# Schema_Attiny_composant.net
KiCad netlist of a schematic drawn in Altium Designer
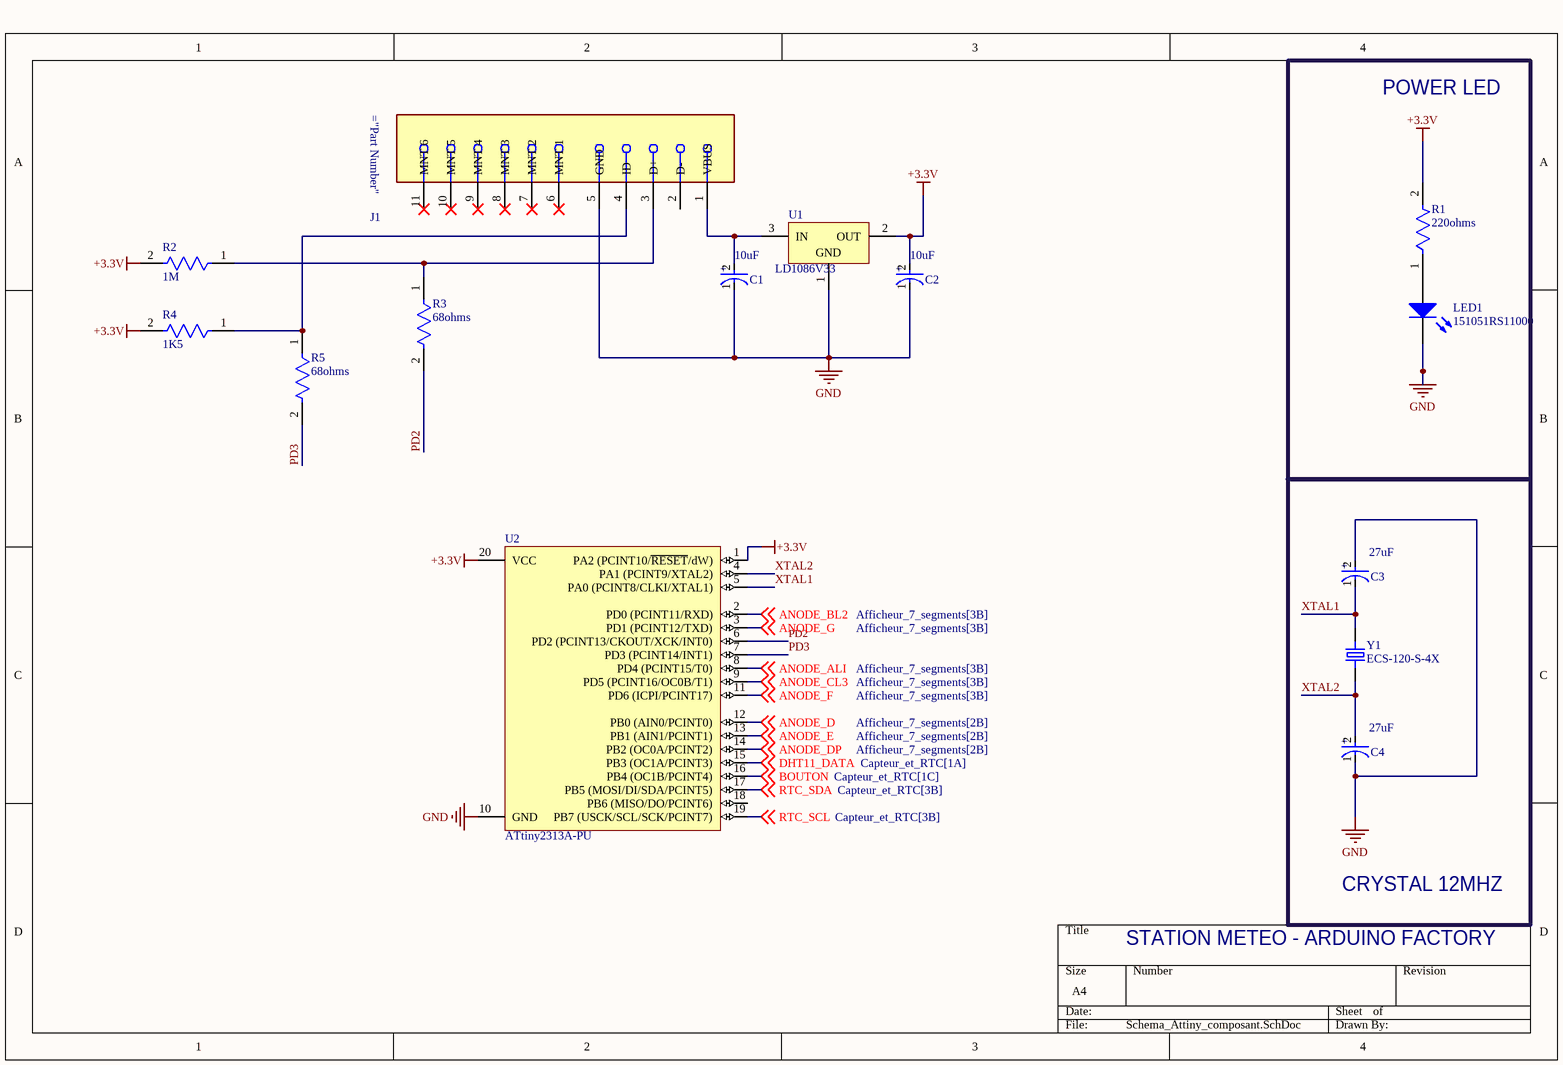
[diagram p0: Schema_Attiny_composant.SchDoc]

(export (version "E")
  (design (tool "Eeschema 10.0.6"))
  (components
    (comp (ref "C1")
      (value "10uF")
      (footprint "Rubycon_0_MFG")
      (libsource (lib "Cap_Rubycon_35ZLH100MEFC6_3X11_eec") (part "35ZLH100MEFC6_3X11"))
    )
    (comp (ref "C2")
      (value "10uF")
      (footprint "Rubycon_0_MFG")
      (libsource (lib "Cap_Rubycon_35ZLH100MEFC6_3X11_eec") (part "35ZLH100MEFC6_3X11"))
    )
    (comp (ref "C3")
      (value "27uF")
      (footprint "Rubycon_0_MFG")
      (libsource (lib "Cap_Rubycon_35ZLH100MEFC6_3X11_eec") (part "35ZLH100MEFC6_3X11"))
    )
    (comp (ref "C4")
      (value "27uF")
      (footprint "Rubycon_0_MFG")
      (libsource (lib "Cap_Rubycon_35ZLH100MEFC6_3X11_eec") (part "35ZLH100MEFC6_3X11"))
    )
    (comp (ref "J1")
      (value "105164-0001")
      (footprint "Molex_105164-0001_0")
      (libsource (lib "Conn_Molex_105164-0001_eec") (part "105164-0001"))
    )
    (comp (ref "LED1")
      (value "151051RS11000")
      (footprint "Type 5mm")
      (description "THT LED round mono-color color lens, WL-TMRW, Red")
      (fields (field (name "MANUFACTURER") "Wuerth Elektronik"))
      (libsource (lib "Wuerth_Elektronik_151051RS11000") (part "151051RS11000"))
    )
    (comp (ref "R1")
      (value "220ohms")
      (footprint "Stackpole_Electronics_Inc._CF14JT1K00_0")
      (libsource (lib "Res_Yageo_MF0207FTE52-10K_eec") (part "MF0207FTE52-10K"))
    )
    (comp (ref "R2")
      (value "1M")
      (footprint "Stackpole_Electronics_Inc._CF14JT1K00_0")
      (libsource (lib "Res_Yageo_MF0207FTE52-10K_eec") (part "MF0207FTE52-10K"))
    )
    (comp (ref "R3")
      (value "68ohms")
      (footprint "Stackpole_Electronics_Inc._CF14JT1K00_0")
      (libsource (lib "Res_Yageo_MF0207FTE52-10K_eec") (part "MF0207FTE52-10K"))
    )
    (comp (ref "R4")
      (value "1K5")
      (footprint "Stackpole_Electronics_Inc._CF14JT1K00_0")
      (libsource (lib "Res_Yageo_MF0207FTE52-10K_eec") (part "MF0207FTE52-10K"))
    )
    (comp (ref "R5")
      (value "68ohms")
      (footprint "Stackpole_Electronics_Inc._CF14JT1K00_0")
      (libsource (lib "Res_Yageo_MF0207FTE52-10K_eec") (part "MF0207FTE52-10K"))
    )
    (comp (ref "U1")
      (value "LD1086V33")
      (footprint "TO220")
      (description "1.5A, Low Drop Positive Voltage Regulator, 3.3V, 3-Pin TO-220")
      (libsource (lib "STMicroelectronics_LD1086V33") (part "LD1086V33"))
    )
    (comp (ref "U2")
      (value "ATtiny2313A-PU")
      (footprint "20P3")
      (fields (field (name "PARTNUMBER") "ATTINY2313A-PU"))
      (libsource (lib "Microchip_Atmel_ATTINY2313A_PU") (part "ATTINY2313A-PU"))
    )
    (comp (ref "Y1")
      (value "ECS-120-S-4X")
      (footprint "XTAL_ECS-120-S-4X")
      (description "CRYSTAL T/H")
      (libsource (lib "ECS-120-S-4X") (part "ECS-120-S-4X"))
    )
  )
  (nets
    (net (code "1") (name "+3.3V") (class "Default")
      (node (ref "C2") (pin "2") (pinfunction "A_2") (pintype "passive"))
      (node (ref "R1") (pin "2") (pinfunction "2_2") (pintype "passive"))
      (node (ref "R2") (pin "2") (pinfunction "2_2") (pintype "passive"))
      (node (ref "R4") (pin "2") (pinfunction "2_2") (pintype "passive"))
      (node (ref "U1") (pin "2") (pinfunction "OUT_2") (pintype "power_in"))
      (node (ref "U2") (pin "1") (pinfunction "PA2_(PCINT10/~{RESET}/dW)_1") (pintype "bidirectional"))
      (node (ref "U2") (pin "20") (pinfunction "VCC_20") (pintype "power_in"))
    )
    (net (code "2") (name "/PD2") (class "Default")
      (node (ref "R3") (pin "2") (pinfunction "2_2") (pintype "passive"))
      (node (ref "U2") (pin "6") (pinfunction "PD2_(PCINT13/CKOUT/XCK/INT0)_6") (pintype "bidirectional"))
    )
    (net (code "3") (name "/PD3") (class "Default")
      (node (ref "R5") (pin "2") (pinfunction "2_2") (pintype "passive"))
      (node (ref "U2") (pin "7") (pinfunction "PD3_(PCINT14/INT1)_7") (pintype "bidirectional"))
    )
    (net (code "4") (name "/XTAL1") (class "Default")
      (node (ref "C3") (pin "1") (pinfunction "C_1") (pintype "passive"))
      (node (ref "U2") (pin "5") (pinfunction "PA0_(PCINT8/CLKI/XTAL1)_5") (pintype "bidirectional"))
      (node (ref "Y1") (pin "2") (pinfunction "2_2") (pintype "passive"))
    )
    (net (code "5") (name "/XTAL2") (class "Default")
      (node (ref "C4") (pin "2") (pinfunction "A_2") (pintype "passive"))
      (node (ref "U2") (pin "4") (pinfunction "PA1_(PCINT9/XTAL2)_4") (pintype "bidirectional"))
      (node (ref "Y1") (pin "1") (pinfunction "1_1") (pintype "passive"))
    )
    (net (code "6") (name "ANODE_ALI") (class "Default")
      (node (ref "U2") (pin "8") (pinfunction "PD4_(PCINT15/T0)_8") (pintype "bidirectional"))
    )
    (net (code "7") (name "ANODE_BL2") (class "Default")
      (node (ref "U2") (pin "2") (pinfunction "PD0_(PCINT11/RXD)_2") (pintype "bidirectional"))
    )
    (net (code "8") (name "ANODE_CL3") (class "Default")
      (node (ref "U2") (pin "9") (pinfunction "PD5_(PCINT16/OC0B/T1)_9") (pintype "bidirectional"))
    )
    (net (code "9") (name "ANODE_D") (class "Default")
      (node (ref "U2") (pin "12") (pinfunction "PB0_(AIN0/PCINT0)_12") (pintype "bidirectional"))
    )
    (net (code "10") (name "ANODE_DP") (class "Default")
      (node (ref "U2") (pin "14") (pinfunction "PB2_(OC0A/PCINT2)_14") (pintype "bidirectional"))
    )
    (net (code "11") (name "ANODE_E") (class "Default")
      (node (ref "U2") (pin "13") (pinfunction "PB1_(AIN1/PCINT1)_13") (pintype "bidirectional"))
    )
    (net (code "12") (name "ANODE_F") (class "Default")
      (node (ref "U2") (pin "11") (pinfunction "PD6_(ICPI/PCINT17)_11") (pintype "bidirectional"))
    )
    (net (code "13") (name "ANODE_G") (class "Default")
      (node (ref "U2") (pin "3") (pinfunction "PD1_(PCINT12/TXD)_3") (pintype "bidirectional"))
    )
    (net (code "14") (name "BOUTON") (class "Default")
      (node (ref "U2") (pin "16") (pinfunction "PB4_(OC1B/PCINT4)_16") (pintype "bidirectional"))
    )
    (net (code "15") (name "DHT11_DATA") (class "Default")
      (node (ref "U2") (pin "15") (pinfunction "PB3_(OC1A/PCINT3)_15") (pintype "bidirectional"))
    )
    (net (code "16") (name "GND") (class "Default")
      (node (ref "C1") (pin "1") (pinfunction "C_1") (pintype "passive"))
      (node (ref "C2") (pin "1") (pinfunction "C_1") (pintype "passive"))
      (node (ref "C3") (pin "2") (pinfunction "A_2") (pintype "passive"))
      (node (ref "C4") (pin "1") (pinfunction "C_1") (pintype "passive"))
      (node (ref "J1") (pin "5") (pinfunction "GND_5") (pintype "passive"))
      (node (ref "LED1") (pin "1") (pinfunction "K_1") (pintype "passive"))
      (node (ref "U1") (pin "1") (pinfunction "GND_1") (pintype "power_in"))
      (node (ref "U2") (pin "10") (pinfunction "GND_10") (pintype "power_in"))
    )
    (net (code "17") (name "Net-(C1-A)") (class "Default")
      (node (ref "C1") (pin "2") (pinfunction "A_2") (pintype "passive"))
      (node (ref "J1") (pin "1") (pinfunction "VBUS_1") (pintype "passive"))
      (node (ref "U1") (pin "3") (pinfunction "IN_3") (pintype "power_in"))
    )
    (net (code "18") (name "Net-(J1-D+)") (class "Default")
      (node (ref "J1") (pin "3") (pinfunction "D+_3") (pintype "passive"))
      (node (ref "R2") (pin "1") (pinfunction "1_1") (pintype "passive"))
      (node (ref "R3") (pin "1") (pinfunction "1_1") (pintype "passive"))
    )
    (net (code "19") (name "Net-(J1-ID)") (class "Default")
      (node (ref "J1") (pin "4") (pinfunction "ID_4") (pintype "passive"))
      (node (ref "R4") (pin "1") (pinfunction "1_1") (pintype "passive"))
      (node (ref "R5") (pin "1") (pinfunction "1_1") (pintype "passive"))
    )
    (net (code "20") (name "Net-(LED1-A)") (class "Default")
      (node (ref "LED1") (pin "2") (pinfunction "A_2") (pintype "passive"))
      (node (ref "R1") (pin "1") (pinfunction "1_1") (pintype "passive"))
    )
    (net (code "21") (name "RTC_SCL") (class "Default")
      (node (ref "U2") (pin "19") (pinfunction "PB7_(USCK/SCL/SCK/PCINT7)_19") (pintype "bidirectional"))
    )
    (net (code "22") (name "RTC_SDA") (class "Default")
      (node (ref "U2") (pin "17") (pinfunction "PB5_(MOSI/DI/SDA/PCINT5)_17") (pintype "bidirectional"))
    )
    (net (code "23") (name "unconnected-(J1-D--Pad2)") (class "Default")
      (node (ref "J1") (pin "2") (pinfunction "D-_2") (pintype "passive"))
    )
    (net (code "24") (name "unconnected-(J1-MNT_1-Pad6)") (class "Default")
      (node (ref "J1") (pin "6") (pinfunction "MNT_1_6") (pintype "passive+no_connect"))
    )
    (net (code "25") (name "unconnected-(J1-MNT_2-Pad7)") (class "Default")
      (node (ref "J1") (pin "7") (pinfunction "MNT_2_7") (pintype "passive+no_connect"))
    )
    (net (code "26") (name "unconnected-(J1-MNT_3-Pad8)") (class "Default")
      (node (ref "J1") (pin "8") (pinfunction "MNT_3_8") (pintype "passive+no_connect"))
    )
    (net (code "27") (name "unconnected-(J1-MNT_4-Pad9)") (class "Default")
      (node (ref "J1") (pin "9") (pinfunction "MNT_4_9") (pintype "passive+no_connect"))
    )
    (net (code "28") (name "unconnected-(J1-MNT_5-Pad10)") (class "Default")
      (node (ref "J1") (pin "10") (pinfunction "MNT_5_10") (pintype "passive+no_connect"))
    )
    (net (code "29") (name "unconnected-(J1-MNT_6-Pad11)") (class "Default")
      (node (ref "J1") (pin "11") (pinfunction "MNT_6_11") (pintype "passive+no_connect"))
    )
    (net (code "30") (name "unconnected-(U2-PB6_(MISO{slash}DO{slash}PCINT6)-Pad18)") (class "Default")
      (node (ref "U2") (pin "18") (pinfunction "PB6_(MISO/DO/PCINT6)_18") (pintype "bidirectional"))
    )
  )
)
